# 214_oled_10.net
KiCad netlist of a schematic drawn in EAGLE
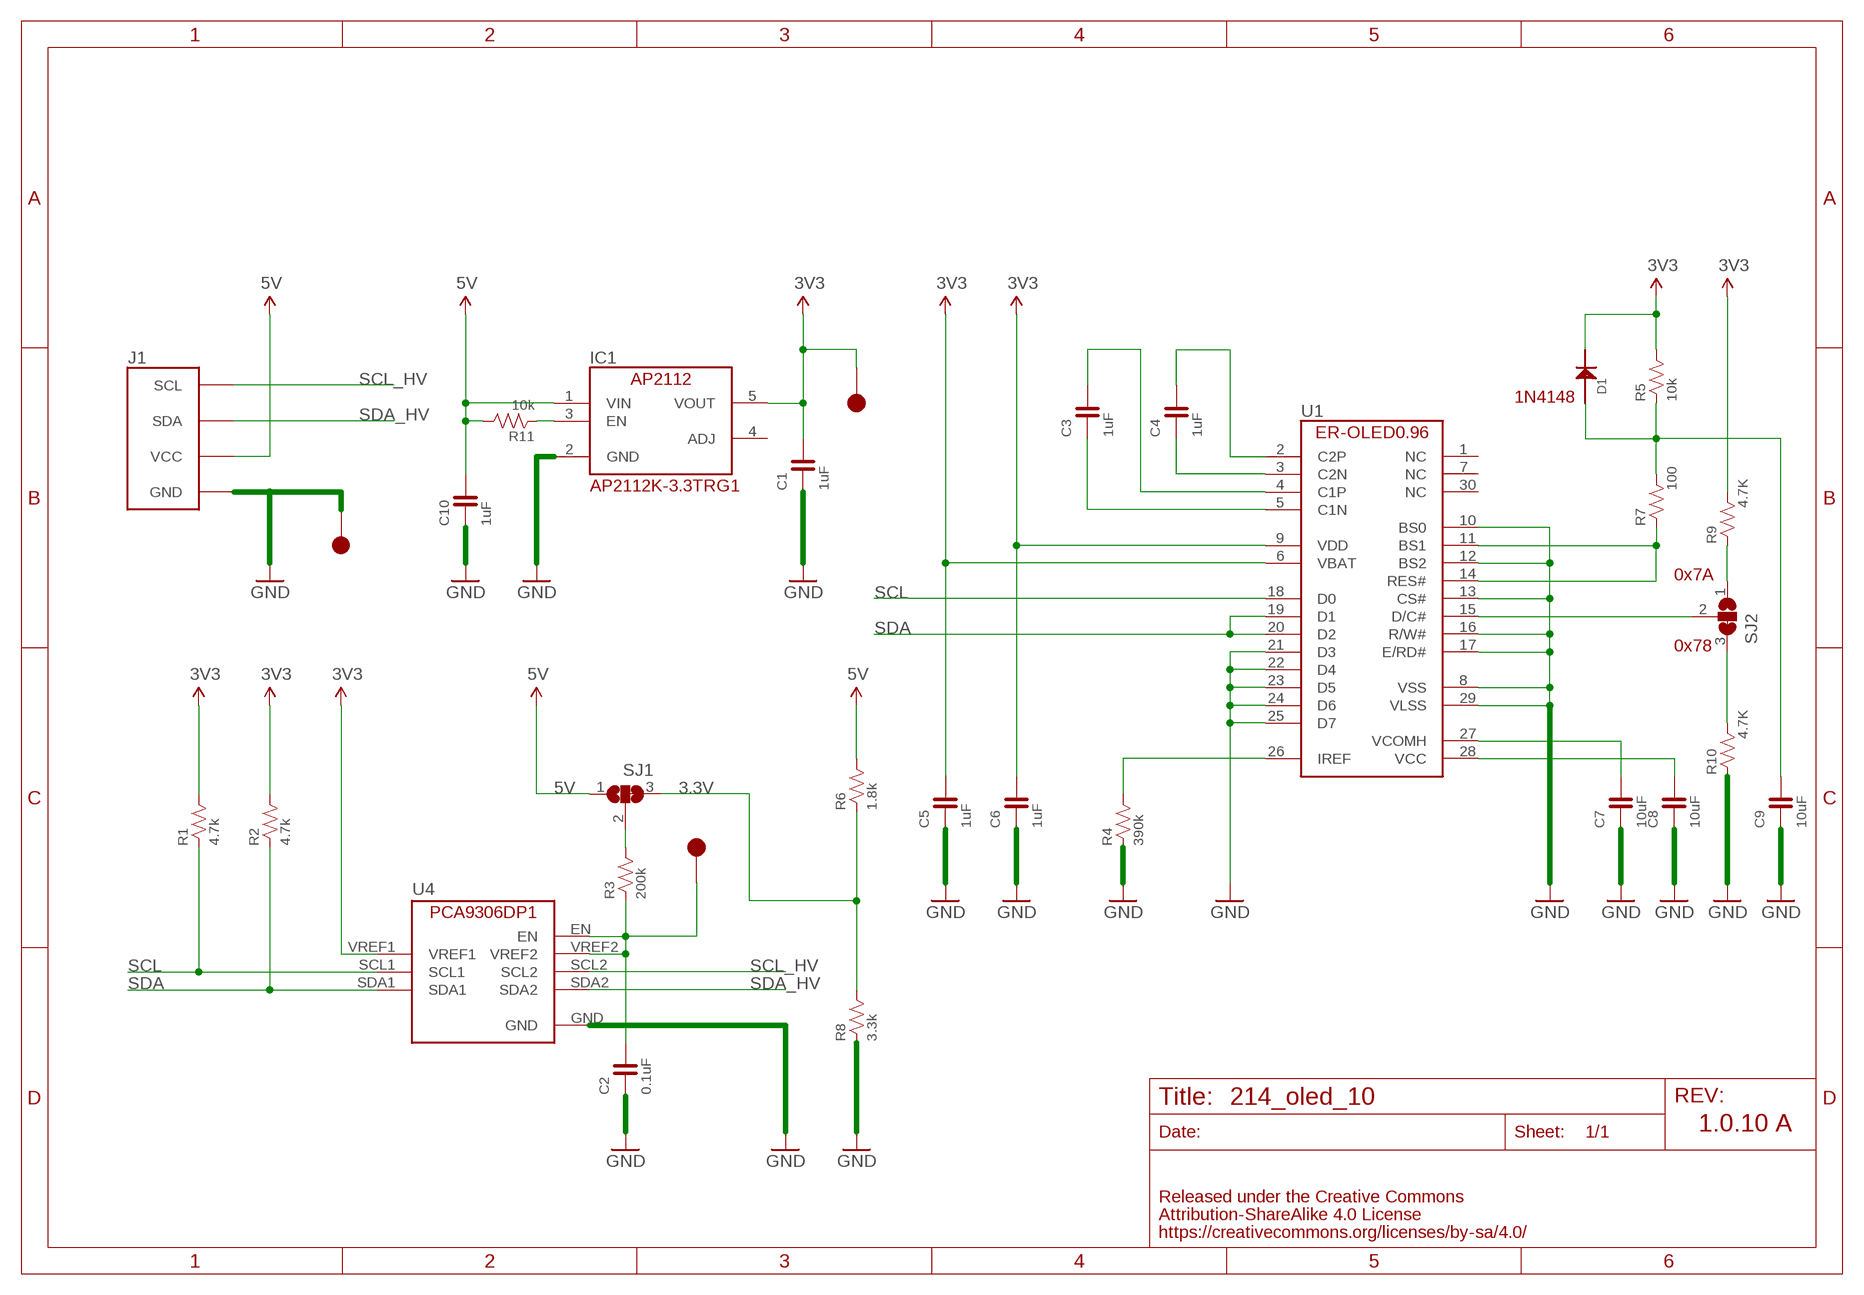
[diagram p0: schematic, sheet 1]

(export (version "E")
  (design (tool "Eeschema 10.0.6"))
  (components
    (comp (ref "C1")
      (value "1uF")
      (footprint "eagle-import:0603")
      (libsource (lib "eagle-import") (part "CAPACITOR-0603"))
    )
    (comp (ref "C2")
      (value "0.1uF")
      (footprint "eagle-import:0603")
      (libsource (lib "eagle-import") (part "CAPACITOR-0603"))
    )
    (comp (ref "C3")
      (value "1uF")
      (footprint "eagle-import:0603")
      (libsource (lib "eagle-import") (part "CAPACITOR-0603"))
    )
    (comp (ref "C4")
      (value "1uF")
      (footprint "eagle-import:0603")
      (libsource (lib "eagle-import") (part "CAPACITOR-0603"))
    )
    (comp (ref "C5")
      (value "1uF")
      (footprint "eagle-import:0603")
      (libsource (lib "eagle-import") (part "CAPACITOR-0603"))
    )
    (comp (ref "C6")
      (value "1uF")
      (footprint "eagle-import:0603")
      (libsource (lib "eagle-import") (part "CAPACITOR-0603"))
    )
    (comp (ref "C7")
      (value "10uF")
      (footprint "eagle-import:0603")
      (libsource (lib "eagle-import") (part "CAPACITOR-0603"))
    )
    (comp (ref "C8")
      (value "10uF")
      (footprint "eagle-import:0603")
      (libsource (lib "eagle-import") (part "CAPACITOR-0603"))
    )
    (comp (ref "C9")
      (value "10uF")
      (footprint "eagle-import:0603")
      (libsource (lib "eagle-import") (part "CAPACITOR-0603"))
    )
    (comp (ref "C10")
      (value "1uF")
      (footprint "eagle-import:0603")
      (libsource (lib "eagle-import") (part "CAPACITOR-0603"))
    )
    (comp (ref "D1")
      (value "1N4148")
      (footprint "eagle-import:1N4148W")
      (libsource (lib "eagle-import") (part "1N4148"))
    )
    (comp (ref "IC1")
      (value "AP2112K-3.3TRG1")
      (footprint "eagle-import:SOT-23-5")
      (libsource (lib "eagle-import") (part "AP2112K-3.3TRG1"))
    )
    (comp (ref "J1")
      (value "FABO_BRICK_I2C-OLED")
      (footprint "eagle-import:FABO_BRICK_I2C_OLED")
      (libsource (lib "eagle-import") (part "FABO_BRICK_I2C-OLED"))
    )
    (comp (ref "R1")
      (value "4.7k")
      (footprint "eagle-import:0603")
      (libsource (lib "eagle-import") (part "RESISTOR-0603"))
    )
    (comp (ref "R2")
      (value "4.7k")
      (footprint "eagle-import:0603")
      (libsource (lib "eagle-import") (part "RESISTOR-0603"))
    )
    (comp (ref "R3")
      (value "200k")
      (footprint "eagle-import:0603")
      (libsource (lib "eagle-import") (part "RESISTOR-0603"))
    )
    (comp (ref "R4")
      (value "390k")
      (footprint "eagle-import:0603")
      (libsource (lib "eagle-import") (part "RESISTOR-0603"))
    )
    (comp (ref "R5")
      (value "10k")
      (footprint "eagle-import:0603")
      (libsource (lib "eagle-import") (part "RESISTOR-0603"))
    )
    (comp (ref "R6")
      (value "1.8k")
      (footprint "eagle-import:0603")
      (libsource (lib "eagle-import") (part "RESISTOR-0603"))
    )
    (comp (ref "R7")
      (value "100")
      (footprint "eagle-import:0603")
      (libsource (lib "eagle-import") (part "RESISTOR-0603"))
    )
    (comp (ref "R8")
      (value "3.3k")
      (footprint "eagle-import:0603")
      (libsource (lib "eagle-import") (part "RESISTOR-0603"))
    )
    (comp (ref "R9")
      (value "4.7K")
      (footprint "eagle-import:0603")
      (libsource (lib "eagle-import") (part "RESISTOR-0603"))
    )
    (comp (ref "R10")
      (value "4.7K")
      (footprint "eagle-import:0603")
      (libsource (lib "eagle-import") (part "RESISTOR-0603"))
    )
    (comp (ref "R11")
      (value "10k")
      (footprint "eagle-import:0603")
      (libsource (lib "eagle-import") (part "RESISTOR-0603"))
    )
    (comp (ref "SJ1")
      (value "SJ2W")
      (footprint "eagle-import:SJ_2")
      (libsource (lib "eagle-import") (part "SJ2W"))
    )
    (comp (ref "SJ2")
      (value "SJ2W")
      (footprint "eagle-import:SJ_2")
      (libsource (lib "eagle-import") (part "SJ2W"))
    )
    (comp (ref "TP1")
      (value "TP-15")
      (footprint "eagle-import:TP-15")
      (libsource (lib "eagle-import") (part "TP-15"))
    )
    (comp (ref "TP2")
      (value "TP-15")
      (footprint "eagle-import:TP-15")
      (libsource (lib "eagle-import") (part "TP-15"))
    )
    (comp (ref "TP5")
      (value "TP-15")
      (footprint "eagle-import:TP-15")
      (libsource (lib "eagle-import") (part "TP-15"))
    )
    (comp (ref "U1")
      (value "ER-OLED0.96-1ER-CON30HT-1")
      (footprint "eagle-import:ER-CON30HT-1")
      (libsource (lib "eagle-import") (part "ER-OLED0.96-1ER-CON30HT-1"))
    )
    (comp (ref "U4")
      (value "PCA9306DP1")
      (footprint "eagle-import:TSSOP8")
      (libsource (lib "eagle-import") (part "PCA9306DP1"))
    )
  )
  (nets
    (net (code "1") (name "/3.3V") (class "Default")
      (node (ref "R6") (pin "1") (pinfunction "1_1") (pintype "bidirectional"))
      (node (ref "R8") (pin "2") (pinfunction "2_2") (pintype "bidirectional"))
      (node (ref "SJ1") (pin "3") (pinfunction "3_3") (pintype "passive"))
    )
    (net (code "2") (name "/SCL") (class "Default")
      (node (ref "R1") (pin "1") (pinfunction "1_1") (pintype "bidirectional"))
      (node (ref "U1") (pin "18") (pinfunction "D0_18") (pintype "bidirectional"))
      (node (ref "U4") (pin "SCL1") (pinfunction "SCL1_SCL1") (pintype "bidirectional"))
    )
    (net (code "3") (name "/SCL_HV") (class "Default")
      (node (ref "J1") (pin "SCL") (pinfunction "SCL_SCL") (pintype "bidirectional"))
      (node (ref "U4") (pin "SCL2") (pinfunction "SCL2_SCL2") (pintype "bidirectional"))
    )
    (net (code "4") (name "/SDA") (class "Default")
      (node (ref "R2") (pin "1") (pinfunction "1_1") (pintype "bidirectional"))
      (node (ref "U1") (pin "19") (pinfunction "D1_19") (pintype "bidirectional"))
      (node (ref "U1") (pin "20") (pinfunction "D2_20") (pintype "bidirectional"))
      (node (ref "U4") (pin "SDA1") (pinfunction "SDA1_SDA1") (pintype "bidirectional"))
    )
    (net (code "5") (name "/SDA_HV") (class "Default")
      (node (ref "J1") (pin "SDA") (pinfunction "SDA_SDA") (pintype "bidirectional"))
      (node (ref "U4") (pin "SDA2") (pinfunction "SDA2_SDA2") (pintype "bidirectional"))
    )
    (net (code "6") (name "3V3") (class "Default")
      (node (ref "C1") (pin "2") (pinfunction "2_2") (pintype "passive"))
      (node (ref "C5") (pin "2") (pinfunction "2_2") (pintype "passive"))
      (node (ref "C6") (pin "2") (pinfunction "2_2") (pintype "passive"))
      (node (ref "D1") (pin "CATHODE") (pinfunction "CATHODE_CATHODE") (pintype "bidirectional"))
      (node (ref "IC1") (pin "5") (pinfunction "VOUT_5") (pintype "bidirectional"))
      (node (ref "R1") (pin "2") (pinfunction "2_2") (pintype "bidirectional"))
      (node (ref "R2") (pin "2") (pinfunction "2_2") (pintype "bidirectional"))
      (node (ref "R5") (pin "2") (pinfunction "2_2") (pintype "bidirectional"))
      (node (ref "R9") (pin "2") (pinfunction "2_2") (pintype "bidirectional"))
      (node (ref "TP5") (pin "1") (pinfunction "1_1") (pintype "bidirectional"))
      (node (ref "U1") (pin "6") (pinfunction "VBAT_6") (pintype "bidirectional"))
      (node (ref "U1") (pin "9") (pinfunction "VDD_9") (pintype "bidirectional"))
      (node (ref "U4") (pin "VREF1") (pinfunction "VREF1_VREF1") (pintype "bidirectional"))
    )
    (net (code "7") (name "5V") (class "Default")
      (node (ref "C10") (pin "2") (pinfunction "2_2") (pintype "passive"))
      (node (ref "IC1") (pin "1") (pinfunction "VIN_1") (pintype "bidirectional"))
      (node (ref "J1") (pin "VCC") (pinfunction "VCC_VCC") (pintype "bidirectional"))
      (node (ref "R11") (pin "2") (pinfunction "2_2") (pintype "bidirectional"))
      (node (ref "R6") (pin "2") (pinfunction "2_2") (pintype "bidirectional"))
      (node (ref "SJ1") (pin "1") (pinfunction "1_1") (pintype "passive"))
    )
    (net (code "8") (name "GND") (class "Default")
      (node (ref "C1") (pin "1") (pinfunction "1_1") (pintype "passive"))
      (node (ref "C10") (pin "1") (pinfunction "1_1") (pintype "passive"))
      (node (ref "C2") (pin "1") (pinfunction "1_1") (pintype "passive"))
      (node (ref "C5") (pin "1") (pinfunction "1_1") (pintype "passive"))
      (node (ref "C6") (pin "1") (pinfunction "1_1") (pintype "passive"))
      (node (ref "C7") (pin "1") (pinfunction "1_1") (pintype "passive"))
      (node (ref "C8") (pin "1") (pinfunction "1_1") (pintype "passive"))
      (node (ref "C9") (pin "1") (pinfunction "1_1") (pintype "passive"))
      (node (ref "IC1") (pin "2") (pinfunction "GND_2") (pintype "bidirectional"))
      (node (ref "J1") (pin "GND") (pinfunction "GND_GND") (pintype "bidirectional"))
      (node (ref "R10") (pin "1") (pinfunction "1_1") (pintype "bidirectional"))
      (node (ref "R4") (pin "1") (pinfunction "1_1") (pintype "bidirectional"))
      (node (ref "R8") (pin "1") (pinfunction "1_1") (pintype "bidirectional"))
      (node (ref "TP1") (pin "1") (pinfunction "1_1") (pintype "bidirectional"))
      (node (ref "U1") (pin "10") (pinfunction "BS0_10") (pintype "bidirectional"))
      (node (ref "U1") (pin "12") (pinfunction "BS2_12") (pintype "bidirectional"))
      (node (ref "U1") (pin "13") (pinfunction "CS#_13") (pintype "bidirectional"))
      (node (ref "U1") (pin "16") (pinfunction "R/W#_16") (pintype "bidirectional"))
      (node (ref "U1") (pin "17") (pinfunction "E/RD#_17") (pintype "bidirectional"))
      (node (ref "U1") (pin "21") (pinfunction "D3_21") (pintype "bidirectional"))
      (node (ref "U1") (pin "22") (pinfunction "D4_22") (pintype "bidirectional"))
      (node (ref "U1") (pin "23") (pinfunction "D5_23") (pintype "bidirectional"))
      (node (ref "U1") (pin "24") (pinfunction "D6_24") (pintype "bidirectional"))
      (node (ref "U1") (pin "25") (pinfunction "D7_25") (pintype "bidirectional"))
      (node (ref "U1") (pin "29") (pinfunction "VLSS_29") (pintype "bidirectional"))
      (node (ref "U1") (pin "8") (pinfunction "VSS_8") (pintype "bidirectional"))
      (node (ref "U4") (pin "GND") (pinfunction "GND_GND") (pintype "bidirectional"))
    )
    (net (code "9") (name "Net-(C2-Pad2)") (class "Default")
      (node (ref "C2") (pin "2") (pinfunction "2_2") (pintype "passive"))
      (node (ref "R3") (pin "1") (pinfunction "1_1") (pintype "bidirectional"))
      (node (ref "TP2") (pin "1") (pinfunction "1_1") (pintype "bidirectional"))
      (node (ref "U4") (pin "EN") (pinfunction "EN_EN") (pintype "bidirectional"))
      (node (ref "U4") (pin "VREF2") (pinfunction "VREF2_VREF2") (pintype "bidirectional"))
    )
    (net (code "10") (name "Net-(C9-Pad2)") (class "Default")
      (node (ref "C9") (pin "2") (pinfunction "2_2") (pintype "passive"))
      (node (ref "D1") (pin "ANODE") (pinfunction "ANODE_ANODE") (pintype "bidirectional"))
      (node (ref "R5") (pin "1") (pinfunction "1_1") (pintype "bidirectional"))
      (node (ref "R7") (pin "2") (pinfunction "2_2") (pintype "bidirectional"))
    )
    (net (code "11") (name "Net-(IC1-EN)") (class "Default")
      (node (ref "IC1") (pin "3") (pinfunction "EN_3") (pintype "bidirectional"))
      (node (ref "R11") (pin "1") (pinfunction "1_1") (pintype "bidirectional"))
    )
    (net (code "12") (name "Net-(R3-Pad2)") (class "Default")
      (node (ref "R3") (pin "2") (pinfunction "2_2") (pintype "bidirectional"))
      (node (ref "SJ1") (pin "2") (pinfunction "2_2") (pintype "passive"))
    )
    (net (code "13") (name "Net-(R9-Pad1)") (class "Default")
      (node (ref "R9") (pin "1") (pinfunction "1_1") (pintype "bidirectional"))
      (node (ref "SJ2") (pin "1") (pinfunction "1_1") (pintype "passive"))
    )
    (net (code "14") (name "Net-(R10-Pad2)") (class "Default")
      (node (ref "R10") (pin "2") (pinfunction "2_2") (pintype "bidirectional"))
      (node (ref "SJ2") (pin "3") (pinfunction "3_3") (pintype "passive"))
    )
    (net (code "15") (name "Net-(U1-BS1)") (class "Default")
      (node (ref "R7") (pin "1") (pinfunction "1_1") (pintype "bidirectional"))
      (node (ref "U1") (pin "11") (pinfunction "BS1_11") (pintype "bidirectional"))
      (node (ref "U1") (pin "14") (pinfunction "RES#_14") (pintype "bidirectional"))
    )
    (net (code "16") (name "Net-(U1-C1N)") (class "Default")
      (node (ref "C3") (pin "1") (pinfunction "1_1") (pintype "passive"))
      (node (ref "U1") (pin "5") (pinfunction "C1N_5") (pintype "bidirectional"))
    )
    (net (code "17") (name "Net-(U1-C1P)") (class "Default")
      (node (ref "C3") (pin "2") (pinfunction "2_2") (pintype "passive"))
      (node (ref "U1") (pin "4") (pinfunction "C1P_4") (pintype "bidirectional"))
    )
    (net (code "18") (name "Net-(U1-C2N)") (class "Default")
      (node (ref "C4") (pin "1") (pinfunction "1_1") (pintype "passive"))
      (node (ref "U1") (pin "3") (pinfunction "C2N_3") (pintype "bidirectional"))
    )
    (net (code "19") (name "Net-(U1-C2P)") (class "Default")
      (node (ref "C4") (pin "2") (pinfunction "2_2") (pintype "passive"))
      (node (ref "U1") (pin "2") (pinfunction "C2P_2") (pintype "bidirectional"))
    )
    (net (code "20") (name "Net-(U1-D{slash}C#)") (class "Default")
      (node (ref "SJ2") (pin "2") (pinfunction "2_2") (pintype "passive"))
      (node (ref "U1") (pin "15") (pinfunction "D/C#_15") (pintype "bidirectional"))
    )
    (net (code "21") (name "Net-(U1-IREF)") (class "Default")
      (node (ref "R4") (pin "2") (pinfunction "2_2") (pintype "bidirectional"))
      (node (ref "U1") (pin "26") (pinfunction "IREF_26") (pintype "bidirectional"))
    )
    (net (code "22") (name "Net-(U1-VCC)") (class "Default")
      (node (ref "C8") (pin "2") (pinfunction "2_2") (pintype "passive"))
      (node (ref "U1") (pin "28") (pinfunction "VCC_28") (pintype "bidirectional"))
    )
    (net (code "23") (name "Net-(U1-VCOMH)") (class "Default")
      (node (ref "C7") (pin "2") (pinfunction "2_2") (pintype "passive"))
      (node (ref "U1") (pin "27") (pinfunction "VCOMH_27") (pintype "bidirectional"))
    )
    (net (code "24") (name "unconnected-(IC1-ADJ-Pad4)") (class "Default")
      (node (ref "IC1") (pin "4") (pinfunction "ADJ_4") (pintype "bidirectional"))
    )
    (net (code "25") (name "unconnected-(U1-NC-Pad1)") (class "Default")
      (node (ref "U1") (pin "1") (pinfunction "NC_1") (pintype "bidirectional"))
    )
    (net (code "26") (name "unconnected-(U1-NC-Pad7)") (class "Default")
      (node (ref "U1") (pin "7") (pinfunction "NC_7") (pintype "bidirectional"))
    )
    (net (code "27") (name "unconnected-(U1-NC-Pad30)") (class "Default")
      (node (ref "U1") (pin "30") (pinfunction "NC_30") (pintype "bidirectional"))
    )
  )
)
